# ESP32.net
KiCad netlist of a schematic drawn in Altium Designer
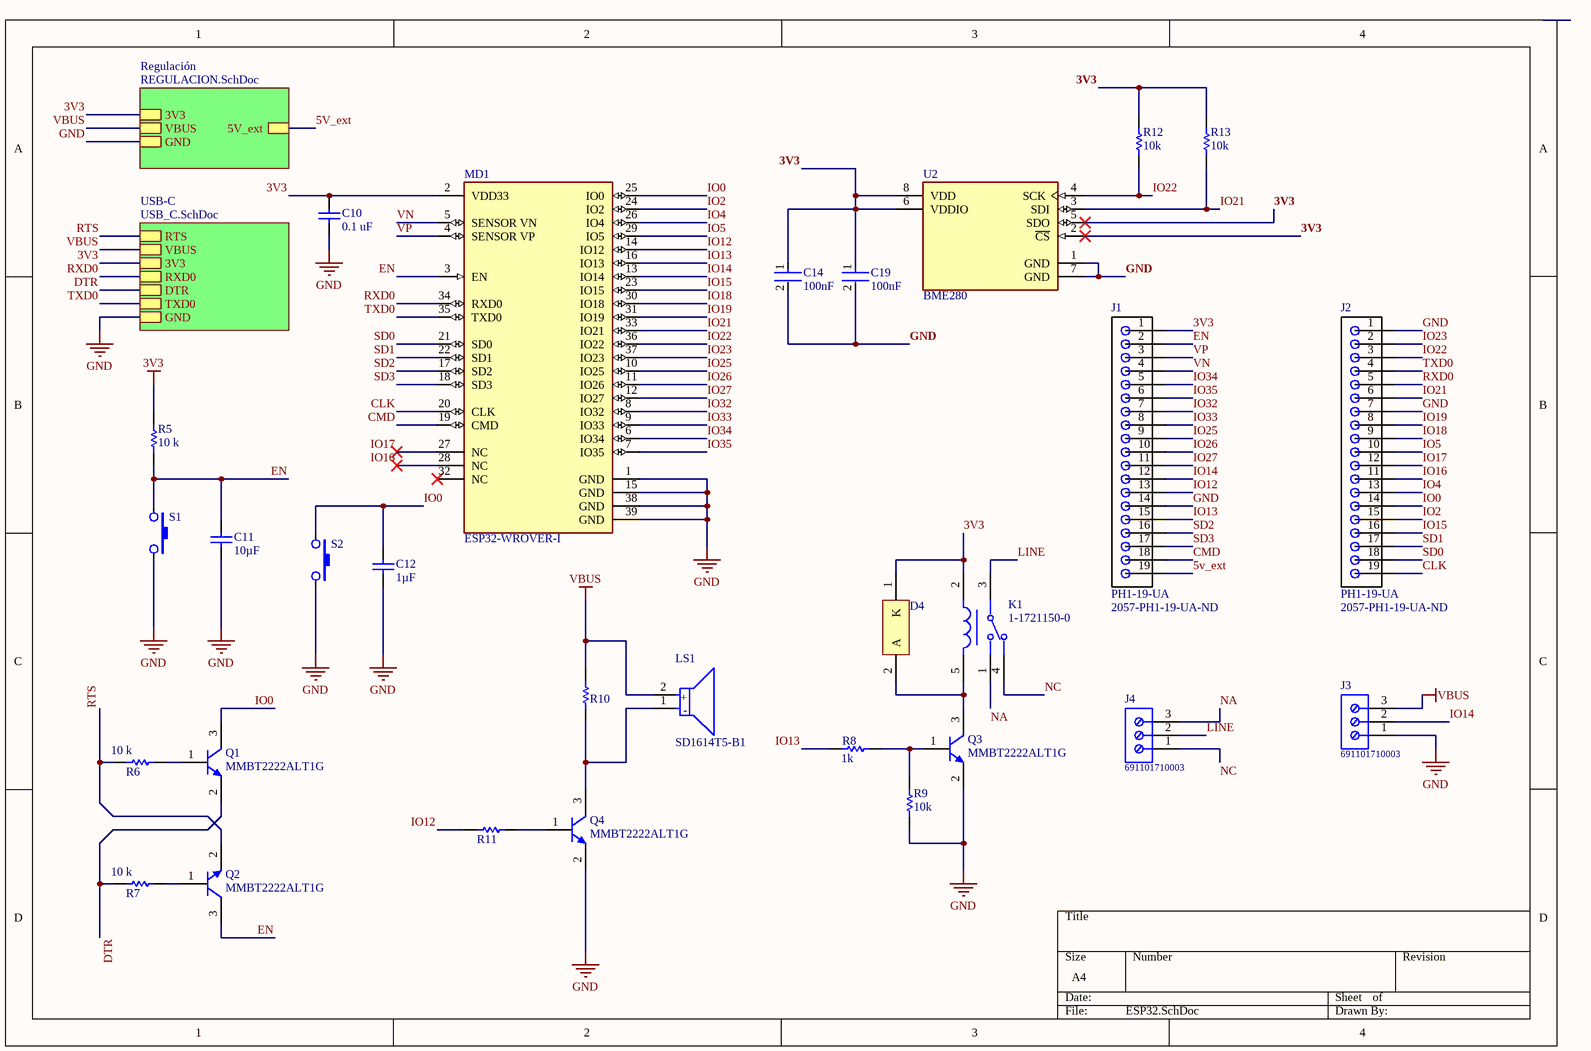
[diagram p0: ESP32.SchDoc]

(export (version "E")
  (design (tool "Eeschema 10.0.6"))
  (components
    (comp (ref "C10")
      (value "0.1 uF")
      (footprint "CAPC2013X94X50ML20T25")
      (description "Chip Capacitor, Ceramic, 0.1 uF, 10%, 50 V, 0805, RoHS, Tape and Reel")
      (fields (field (name "MANUFACTURER") "AVX"))
      (libsource (lib "Altium Content Vault") (part "CAP-NP-2"))
    )
    (comp (ref "C11")
      (value "10µF")
      (footprint "CAPC2013X145X50ML20T25")
      (description "1µF ±10% 16V Ceramic Capacitor X7R 0805 (2012 Metric)")
      (fields (field (name "MANUFACTURER") "Kemet") (field (name "PART NUMBER") "C0805C105K4RAC7800"))
      (libsource (lib "Altium Content Vault") (part "CAP"))
    )
    (comp (ref "C12")
      (value "1µF")
      (footprint "CAPC2013X145X50ML20T25")
      (description "1µF ±10% 16V Ceramic Capacitor X7R 0805 (2012 Metric)")
      (fields (field (name "MANUFACTURER") "Kemet") (field (name "PART NUMBER") "C0805C105K4RAC7800"))
      (libsource (lib "Altium Content Vault") (part "CAP"))
    )
    (comp (ref "C14")
      (value "100nF")
      (footprint "FP-C0805C-DN-IPC_A")
      (description "CAP CER 0.1UF 50V X7R 0805")
      (fields
        (field (name "MANUFACTURER PART NUMBER") "C0805C104K5RACTU")
        (field (name "MANUFACTURER") "KEMET")
      )
      (libsource (lib "Altium Content Vault") (part "b4654b650e69147ec39a6b967a45e02"))
    )
    (comp (ref "C19")
      (value "100nF")
      (footprint "FP-C0805C-DN-IPC_A")
      (description "CAP CER 0.1UF 50V X7R 0805")
      (fields
        (field (name "MANUFACTURER PART NUMBER") "C0805C104K5RACTU")
        (field (name "MANUFACTURER") "KEMET")
      )
      (libsource (lib "Altium Content Vault") (part "b4654b650e69147ec39a6b967a45e02"))
    )
    (comp (ref "D4")
      (value "MBR120ESFT1G")
      (footprint "ONSC-SOD-123FL-2-498_V")
      (description "Schottky Power Rectifier, 2-Pin SOD-123, Pb-Free, Tape and Reel")
      (fields (field (name "MANUFACTURER") "On Semiconductor"))
      (libsource (lib "Altium Content Vault") (part "ONSC-D-K1A2-2_A"))
    )
    (comp (ref "J1")
      (value "PH1-19-UA")
      (footprint "PH1-19-UA")
      (description "Connector Header Through Hole 19 position 0.100\" (2.54mm)")
      (fields (field (name "SUPPLIER PART NUMBER 1") "2057-PH1-19-UA-ND"))
      (libsource (lib "") (part "PH1-19-UA_1"))
    )
    (comp (ref "J2")
      (value "PH1-19-UA")
      (footprint "PH1-19-UA")
      (description "Connector Header Through Hole 19 position 0.100\" (2.54mm)")
      (fields (field (name "SUPPLIER PART NUMBER 1") "2057-PH1-19-UA-ND"))
      (libsource (lib "Isidro_Library") (part "PH1-19-UA"))
    )
    (comp (ref "J3")
      (value "691101710003")
      (footprint "691101710003")
      (description "Series 101 - 5.00 mm Horizontal Entry Modular with Pressure Clamp WR-TBL, 3 pin")
      (fields (field (name "MANUFACTURER") "Wurth Elektronik") (field (name "PUBLISHER") "WurthElektronik"))
      (libsource (lib "Altium Content Vault") (part "WE-CN-1P-F-TB3"))
    )
    (comp (ref "J4")
      (value "691101710003")
      (footprint "691101710003")
      (description "Series 101 - 5.00 mm Horizontal Entry Modular with Pressure Clamp WR-TBL, 3 pin")
      (fields (field (name "MANUFACTURER") "Wurth Elektronik") (field (name "PUBLISHER") "WurthElektronik"))
      (libsource (lib "Altium Content Vault") (part "WE-CN-1P-F-TB3"))
    )
    (comp (ref "K1")
      (value "1-1721150-0")
      (footprint "FP-1-1721150-0-MFG")
      (description "RELAY GEN PURPOSE SPDT 10A 5V")
      (fields
        (field (name "MANUFACTURER") "TE")
        (field (name "OCTOPART") "https://octopart.com/1-1721150-0-te+connectivity-41294869")
      )
      (libsource (lib "Altium Content Vault") (part "6d7f6cec76f9d90da65a396cf24d809"))
    )
    (comp (ref "LS1")
      (value "SD1614T5-B1")
      (footprint "FP-SD1614T5-B1-MFG")
      (description "AUDIO MAGNETIC XDCR 3-6V TH")
      (libsource (lib "Altium Content Vault") (part "f7ec632b6fea80cbef86dc3340f200c"))
    )
    (comp (ref "MD1")
      (value "ESP32-WROVER-I")
      (footprint "FP-ESP32-WROVER-I-MFG")
      (description "SMD MODULE, ESP32-D0WDQ6, 32MBIT")
      (fields
        (field (name "MANUFACTURER") "Espressif")
        (field (name "OCTOPART") "https://octopart.com/esp32-wrover-i-espressif+systems-89171349")
      )
      (libsource (lib "Altium Content Vault") (part "cbbb37af8bcfe61dfd46ac9418f0340"))
    )
    (comp (ref "Q1")
      (value "MMBT2222ALT1G")
      (footprint "ONSC-SOT-23-3-318-08_V")
      (description "General Purpose Transistor, NPN Silicon, 3-Pin SOT-23, Pb-Free, Tape and Reel")
      (fields (field (name "MANUFACTURER") "On Semiconductor"))
      (libsource (lib "Altium Content Vault") (part "ONSC-NPN-B1E2C3-3"))
    )
    (comp (ref "Q2")
      (value "MMBT2222ALT1G")
      (footprint "ONSC-SOT-23-3-318-08_V")
      (description "General Purpose Transistor, NPN Silicon, 3-Pin SOT-23, Pb-Free, Tape and Reel")
      (fields (field (name "MANUFACTURER") "On Semiconductor"))
      (libsource (lib "Altium Content Vault") (part "ONSC-NPN-B1E2C3-3"))
    )
    (comp (ref "Q3")
      (value "MMBT2222ALT1G")
      (footprint "ONSC-SOT-23-3-318-08_V")
      (description "General Purpose Transistor, NPN Silicon, 3-Pin SOT-23, Pb-Free, Tape and Reel")
      (fields (field (name "MANUFACTURER") "On Semiconductor"))
      (libsource (lib "Altium Content Vault") (part "ONSC-NPN-B1E2C3-3"))
    )
    (comp (ref "Q4")
      (value "MMBT2222ALT1G")
      (footprint "ONSC-SOT-23-3-318-08_V")
      (description "General Purpose Transistor, NPN Silicon, 3-Pin SOT-23, Pb-Free, Tape and Reel")
      (fields (field (name "MANUFACTURER") "On Semiconductor"))
      (libsource (lib "Altium Content Vault") (part "ONSC-NPN-B1E2C3-3"))
    )
    (comp (ref "R5")
      (value "10 k")
      (footprint "RESC2013X60X30ML20T20")
      (fields (field (name "PART NUMBER") "RK73B2ATTD103J") (field (name "MANUFACTURER") "KOA Speer"))
      (libsource (lib "Altium Content Vault") (part "RES"))
    )
    (comp (ref "R6")
      (value "10 k")
      (footprint "RESC2013X60X30ML20T20")
      (fields (field (name "PART NUMBER") "RK73B2ATTD103J") (field (name "MANUFACTURER") "KOA Speer"))
      (libsource (lib "Altium Content Vault") (part "RES"))
    )
    (comp (ref "R7")
      (value "10 k")
      (footprint "RESC2013X60X30ML20T20")
      (fields (field (name "PART NUMBER") "RK73B2ATTD103J") (field (name "MANUFACTURER") "KOA Speer"))
      (libsource (lib "Altium Content Vault") (part "RES"))
    )
    (comp (ref "R8")
      (value "1k")
      (footprint "RESC2013X60X30ML20T20")
      (fields (field (name "PART NUMBER") "RK73B2ATTD103J") (field (name "MANUFACTURER") "KOA Speer"))
      (libsource (lib "Altium Content Vault") (part "RES"))
    )
    (comp (ref "R9")
      (value "10k")
      (footprint "RESC2013X60X30ML20T20")
      (fields (field (name "PART NUMBER") "RK73B2ATTD103J") (field (name "MANUFACTURER") "KOA Speer"))
      (libsource (lib "Altium Content Vault") (part "RES"))
    )
    (comp (ref "R10")
      (value "ERJ-P06J102V")
      (footprint "RESC2013X70X40ML20T20")
      (description "RES SMD 1K OHM 5% 1/2W 0805")
      (fields (field (name "MANUFACTURER") "Panasonic"))
      (libsource (lib "Altium Content Vault") (part "RES"))
    )
    (comp (ref "R11")
      (value "RK73B2ATTD103J")
      (footprint "RESC2013X60X30ML20T20")
      (fields (field (name "MANUFACTURER") "KOA Speer"))
      (libsource (lib "Altium Content Vault") (part "RES"))
    )
    (comp (ref "R12")
      (value "10k")
      (footprint "RESC2013X60X40ML20T25_A")
      (fields (field (name "TOLERANCE") "0.1%") (field (name "MANUFACTURER") "Panasonic"))
      (libsource (lib "Altium Content Vault") (part "RES-2"))
    )
    (comp (ref "R13")
      (value "10k")
      (footprint "RESC2013X60X40ML20T25_A")
      (fields (field (name "TOLERANCE") "0.1%") (field (name "MANUFACTURER") "Panasonic"))
      (libsource (lib "Altium Content Vault") (part "RES-2"))
    )
    (comp (ref "S1")
      (value "PTS820J25MSMTRLFS")
      (footprint "SMT_SW_PTS_820")
      (libsource (lib "SnapEDAsch") (part "PTS820J25MSMTRLFS"))
    )
    (comp (ref "S2")
      (value "IO0")
      (footprint "SMT_SW_PTS_820")
      (libsource (lib "SnapEDAsch") (part "PTS820J25MSMTRLFS"))
    )
    (comp (ref "U2")
      (value "BME280")
      (footprint "FP-BME280-MFG")
      (description "SENSOR PRESSURE HUMIDITY TEMP")
      (libsource (lib "Altium Content Vault") (part "d58e2f6669bc67e6a2bc6a28610ca79"))
    )
  )
  (nets
    (net (code "2") (name "/5v_ext") (class "Default")
      (node (ref "J1") (pin "19") (pinfunction "19_19") (pintype "passive"))
    )
    (net (code "3") (name "/CLK") (class "Default")
      (node (ref "J2") (pin "19") (pinfunction "19_19") (pintype "passive"))
      (node (ref "MD1") (pin "20") (pinfunction "CLK_20") (pintype "bidirectional"))
    )
    (net (code "4") (name "/CMD") (class "Default")
      (node (ref "J1") (pin "18") (pinfunction "18_18") (pintype "passive"))
      (node (ref "MD1") (pin "19") (pinfunction "CMD_19") (pintype "bidirectional"))
    )
    (net (code "5") (name "/DTR") (class "Default")
      (node (ref "Q1") (pin "2") (pinfunction "E_2") (pintype "passive"))
      (node (ref "R7") (pin "2") (pinfunction "2_2") (pintype "passive"))
    )
    (net (code "6") (name "/EN") (class "Default")
      (node (ref "C11") (pin "2") (pinfunction "2_2") (pintype "passive"))
      (node (ref "J1") (pin "2") (pinfunction "2_2") (pintype "passive"))
      (node (ref "MD1") (pin "3") (pinfunction "EN_3") (pintype "input"))
      (node (ref "Q2") (pin "3") (pinfunction "C_3") (pintype "passive"))
      (node (ref "R5") (pin "1") (pinfunction "1_1") (pintype "passive"))
      (node (ref "S1") (pin "1") (pinfunction "1_1") (pintype "passive"))
    )
    (net (code "7") (name "/IO0") (class "Default")
      (node (ref "C12") (pin "2") (pinfunction "2_2") (pintype "passive"))
      (node (ref "J2") (pin "14") (pinfunction "14_14") (pintype "passive"))
      (node (ref "MD1") (pin "25") (pinfunction "IO0_25") (pintype "bidirectional"))
      (node (ref "Q1") (pin "3") (pinfunction "C_3") (pintype "passive"))
      (node (ref "S2") (pin "1") (pinfunction "1_1") (pintype "passive"))
    )
    (net (code "8") (name "/IO2") (class "Default")
      (node (ref "J2") (pin "15") (pinfunction "15_15") (pintype "passive"))
      (node (ref "MD1") (pin "24") (pinfunction "IO2_24") (pintype "bidirectional"))
    )
    (net (code "9") (name "/IO4") (class "Default")
      (node (ref "J2") (pin "13") (pinfunction "13_13") (pintype "passive"))
      (node (ref "MD1") (pin "26") (pinfunction "IO4_26") (pintype "bidirectional"))
    )
    (net (code "10") (name "/IO5") (class "Default")
      (node (ref "J2") (pin "10") (pinfunction "10_10") (pintype "passive"))
      (node (ref "MD1") (pin "29") (pinfunction "IO5_29") (pintype "bidirectional"))
    )
    (net (code "11") (name "/IO12") (class "Default")
      (node (ref "J1") (pin "13") (pinfunction "13_13") (pintype "passive"))
      (node (ref "MD1") (pin "14") (pinfunction "IO12_14") (pintype "bidirectional"))
      (node (ref "R11") (pin "1") (pinfunction "1_1") (pintype "passive"))
    )
    (net (code "12") (name "/IO13") (class "Default")
      (node (ref "J1") (pin "15") (pinfunction "15_15") (pintype "passive"))
      (node (ref "MD1") (pin "16") (pinfunction "IO13_16") (pintype "bidirectional"))
      (node (ref "R8") (pin "1") (pinfunction "1_1") (pintype "passive"))
    )
    (net (code "13") (name "/IO14") (class "Default")
      (node (ref "J1") (pin "12") (pinfunction "12_12") (pintype "passive"))
      (node (ref "J3") (pin "2") (pinfunction "2_2") (pintype "passive"))
      (node (ref "MD1") (pin "13") (pinfunction "IO14_13") (pintype "bidirectional"))
    )
    (net (code "14") (name "/IO15") (class "Default")
      (node (ref "J2") (pin "16") (pinfunction "16_16") (pintype "passive"))
      (node (ref "MD1") (pin "23") (pinfunction "IO15_23") (pintype "bidirectional"))
    )
    (net (code "15") (name "/IO16") (class "Default")
      (node (ref "J2") (pin "11") (pinfunction "11_11") (pintype "passive"))
      (node (ref "MD1") (pin "28") (pinfunction "NC_28") (pintype "passive"))
    )
    (net (code "16") (name "/IO17") (class "Default")
      (node (ref "J2") (pin "12") (pinfunction "12_12") (pintype "passive"))
      (node (ref "MD1") (pin "27") (pinfunction "NC_27") (pintype "passive"))
    )
    (net (code "17") (name "/IO18") (class "Default")
      (node (ref "J2") (pin "9") (pinfunction "9_9") (pintype "passive"))
      (node (ref "MD1") (pin "30") (pinfunction "IO18_30") (pintype "bidirectional"))
    )
    (net (code "18") (name "/IO19") (class "Default")
      (node (ref "J2") (pin "8") (pinfunction "8_8") (pintype "passive"))
      (node (ref "MD1") (pin "31") (pinfunction "IO19_31") (pintype "bidirectional"))
    )
    (net (code "19") (name "/IO21") (class "Default")
      (node (ref "J2") (pin "6") (pinfunction "6_6") (pintype "passive"))
      (node (ref "MD1") (pin "33") (pinfunction "IO21_33") (pintype "bidirectional"))
      (node (ref "R13") (pin "1") (pinfunction "1_1") (pintype "passive"))
      (node (ref "U2") (pin "3") (pinfunction "SDI_3") (pintype "bidirectional"))
    )
    (net (code "20") (name "/IO22") (class "Default")
      (node (ref "J2") (pin "3") (pinfunction "3_3") (pintype "passive"))
      (node (ref "MD1") (pin "36") (pinfunction "IO22_36") (pintype "bidirectional"))
      (node (ref "R12") (pin "1") (pinfunction "1_1") (pintype "passive"))
      (node (ref "U2") (pin "4") (pinfunction "SCK_4") (pintype "input"))
    )
    (net (code "21") (name "/IO23") (class "Default")
      (node (ref "J2") (pin "2") (pinfunction "2_2") (pintype "passive"))
      (node (ref "MD1") (pin "37") (pinfunction "IO23_37") (pintype "bidirectional"))
    )
    (net (code "22") (name "/IO25") (class "Default")
      (node (ref "J1") (pin "9") (pinfunction "9_9") (pintype "passive"))
      (node (ref "MD1") (pin "10") (pinfunction "IO25_10") (pintype "bidirectional"))
    )
    (net (code "23") (name "/IO26") (class "Default")
      (node (ref "J1") (pin "10") (pinfunction "10_10") (pintype "passive"))
      (node (ref "MD1") (pin "11") (pinfunction "IO26_11") (pintype "bidirectional"))
    )
    (net (code "24") (name "/IO27") (class "Default")
      (node (ref "J1") (pin "11") (pinfunction "11_11") (pintype "passive"))
      (node (ref "MD1") (pin "12") (pinfunction "IO27_12") (pintype "bidirectional"))
    )
    (net (code "25") (name "/IO32") (class "Default")
      (node (ref "J1") (pin "7") (pinfunction "7_7") (pintype "passive"))
      (node (ref "MD1") (pin "8") (pinfunction "IO32_8") (pintype "bidirectional"))
    )
    (net (code "26") (name "/IO33") (class "Default")
      (node (ref "J1") (pin "8") (pinfunction "8_8") (pintype "passive"))
      (node (ref "MD1") (pin "9") (pinfunction "IO33_9") (pintype "bidirectional"))
    )
    (net (code "27") (name "/IO34") (class "Default")
      (node (ref "J1") (pin "5") (pinfunction "5_5") (pintype "passive"))
      (node (ref "MD1") (pin "6") (pinfunction "IO34_6") (pintype "bidirectional"))
    )
    (net (code "28") (name "/IO35") (class "Default")
      (node (ref "J1") (pin "6") (pinfunction "6_6") (pintype "passive"))
      (node (ref "MD1") (pin "7") (pinfunction "IO35_7") (pintype "bidirectional"))
    )
    (net (code "29") (name "/LINE") (class "Default")
      (node (ref "J4") (pin "2") (pinfunction "2_2") (pintype "passive"))
      (node (ref "K1") (pin "3") (pinfunction "3_3") (pintype "passive"))
    )
    (net (code "30") (name "/NA") (class "Default")
      (node (ref "J4") (pin "3") (pinfunction "3_3") (pintype "passive"))
      (node (ref "K1") (pin "1") (pinfunction "1_1") (pintype "passive"))
    )
    (net (code "31") (name "/NC") (class "Default")
      (node (ref "J4") (pin "1") (pinfunction "1_1") (pintype "passive"))
      (node (ref "K1") (pin "4") (pinfunction "4_4") (pintype "passive"))
    )
    (net (code "32") (name "/RTS") (class "Default")
      (node (ref "Q2") (pin "2") (pinfunction "E_2") (pintype "passive"))
      (node (ref "R6") (pin "2") (pinfunction "2_2") (pintype "passive"))
    )
    (net (code "33") (name "/RXD0") (class "Default")
      (node (ref "J2") (pin "5") (pinfunction "5_5") (pintype "passive"))
      (node (ref "MD1") (pin "34") (pinfunction "RXD0_34") (pintype "bidirectional"))
    )
    (net (code "34") (name "/SD0") (class "Default")
      (node (ref "J2") (pin "18") (pinfunction "18_18") (pintype "passive"))
      (node (ref "MD1") (pin "21") (pinfunction "SD0_21") (pintype "bidirectional"))
    )
    (net (code "35") (name "/SD1") (class "Default")
      (node (ref "J2") (pin "17") (pinfunction "17_17") (pintype "passive"))
      (node (ref "MD1") (pin "22") (pinfunction "SD1_22") (pintype "bidirectional"))
    )
    (net (code "36") (name "/SD2") (class "Default")
      (node (ref "J1") (pin "16") (pinfunction "16_16") (pintype "passive"))
      (node (ref "MD1") (pin "17") (pinfunction "SD2_17") (pintype "bidirectional"))
    )
    (net (code "37") (name "/SD3") (class "Default")
      (node (ref "J1") (pin "17") (pinfunction "17_17") (pintype "passive"))
      (node (ref "MD1") (pin "18") (pinfunction "SD3_18") (pintype "bidirectional"))
    )
    (net (code "38") (name "/TXD0") (class "Default")
      (node (ref "J2") (pin "4") (pinfunction "4_4") (pintype "passive"))
      (node (ref "MD1") (pin "35") (pinfunction "TXD0_35") (pintype "bidirectional"))
    )
    (net (code "39") (name "/VN") (class "Default")
      (node (ref "J1") (pin "4") (pinfunction "4_4") (pintype "passive"))
      (node (ref "MD1") (pin "5") (pinfunction "SENSOR_VN_5") (pintype "bidirectional"))
    )
    (net (code "40") (name "/VP") (class "Default")
      (node (ref "J1") (pin "3") (pinfunction "3_3") (pintype "passive"))
      (node (ref "MD1") (pin "4") (pinfunction "SENSOR_VP_4") (pintype "bidirectional"))
    )
    (net (code "41") (name "3V3") (class "Default")
      (node (ref "C10") (pin "2") (pinfunction "2_2") (pintype "passive"))
      (node (ref "C14") (pin "1") (pinfunction "1_1") (pintype "passive"))
      (node (ref "C19") (pin "1") (pinfunction "1_1") (pintype "passive"))
      (node (ref "D4") (pin "1") (pinfunction "K_1") (pintype "passive"))
      (node (ref "J1") (pin "1") (pinfunction "1_1") (pintype "passive"))
      (node (ref "K1") (pin "2") (pinfunction "2_2") (pintype "passive"))
      (node (ref "MD1") (pin "2") (pinfunction "VDD33_2") (pintype "power_in"))
      (node (ref "R12") (pin "2") (pinfunction "2_2") (pintype "passive"))
      (node (ref "R13") (pin "2") (pinfunction "2_2") (pintype "passive"))
      (node (ref "R5") (pin "2") (pinfunction "2_2") (pintype "passive"))
      (node (ref "U2") (pin "2") (pinfunction "~{CS}_2") (pintype "input"))
      (node (ref "U2") (pin "5") (pinfunction "SDO_5") (pintype "bidirectional"))
      (node (ref "U2") (pin "6") (pinfunction "VDDIO_6") (pintype "power_in"))
      (node (ref "U2") (pin "8") (pinfunction "VDD_8") (pintype "power_in"))
    )
    (net (code "42") (name "GND") (class "Default")
      (node (ref "C10") (pin "1") (pinfunction "1_1") (pintype "passive"))
      (node (ref "C11") (pin "1") (pinfunction "1_1") (pintype "passive"))
      (node (ref "C12") (pin "1") (pinfunction "1_1") (pintype "passive"))
      (node (ref "C14") (pin "2") (pinfunction "2_2") (pintype "passive"))
      (node (ref "C19") (pin "2") (pinfunction "2_2") (pintype "passive"))
      (node (ref "J1") (pin "14") (pinfunction "14_14") (pintype "passive"))
      (node (ref "J2") (pin "1") (pinfunction "1_1") (pintype "passive"))
      (node (ref "J2") (pin "7") (pinfunction "7_7") (pintype "passive"))
      (node (ref "J3") (pin "1") (pinfunction "1_1") (pintype "passive"))
      (node (ref "MD1") (pin "1") (pinfunction "GND_1") (pintype "power_in"))
      (node (ref "MD1") (pin "15") (pinfunction "GND_15") (pintype "power_in"))
      (node (ref "MD1") (pin "38") (pinfunction "GND_38") (pintype "power_in"))
      (node (ref "MD1") (pin "39") (pinfunction "GND_39") (pintype "power_in"))
      (node (ref "Q3") (pin "2") (pinfunction "E_2") (pintype "passive"))
      (node (ref "Q4") (pin "2") (pinfunction "E_2") (pintype "passive"))
      (node (ref "R9") (pin "2") (pinfunction "2_2") (pintype "passive"))
      (node (ref "S1") (pin "2") (pinfunction "2_2") (pintype "passive"))
      (node (ref "S2") (pin "2") (pinfunction "2_2") (pintype "passive"))
      (node (ref "U2") (pin "1") (pinfunction "GND_1") (pintype "power_in"))
      (node (ref "U2") (pin "7") (pinfunction "GND_7") (pintype "power_in"))
    )
    (net (code "43") (name "Net-(D4-A)") (class "Default")
      (node (ref "D4") (pin "2") (pinfunction "A_2") (pintype "passive"))
      (node (ref "K1") (pin "5") (pinfunction "5_5") (pintype "passive"))
      (node (ref "Q3") (pin "3") (pinfunction "C_3") (pintype "passive"))
    )
    (net (code "44") (name "Net-(LS1-C)") (class "Default")
      (node (ref "LS1") (pin "1") (pinfunction "C_1") (pintype "passive"))
      (node (ref "Q4") (pin "3") (pinfunction "C_3") (pintype "passive"))
      (node (ref "R10") (pin "1") (pinfunction "1_1") (pintype "passive"))
    )
    (net (code "45") (name "Net-(Q1-B)") (class "Default")
      (node (ref "Q1") (pin "1") (pinfunction "B_1") (pintype "passive"))
      (node (ref "R6") (pin "1") (pinfunction "1_1") (pintype "passive"))
    )
    (net (code "46") (name "Net-(Q2-B)") (class "Default")
      (node (ref "Q2") (pin "1") (pinfunction "B_1") (pintype "passive"))
      (node (ref "R7") (pin "1") (pinfunction "1_1") (pintype "passive"))
    )
    (net (code "47") (name "Net-(Q3-B)") (class "Default")
      (node (ref "Q3") (pin "1") (pinfunction "B_1") (pintype "passive"))
      (node (ref "R8") (pin "2") (pinfunction "2_2") (pintype "passive"))
      (node (ref "R9") (pin "1") (pinfunction "1_1") (pintype "passive"))
    )
    (net (code "48") (name "Net-(Q4-B)") (class "Default")
      (node (ref "Q4") (pin "1") (pinfunction "B_1") (pintype "passive"))
      (node (ref "R11") (pin "2") (pinfunction "2_2") (pintype "passive"))
    )
    (net (code "49") (name "VBUS") (class "Default")
      (node (ref "J3") (pin "3") (pinfunction "3_3") (pintype "passive"))
      (node (ref "LS1") (pin "2") (pinfunction "A_2") (pintype "passive"))
      (node (ref "R10") (pin "2") (pinfunction "2_2") (pintype "passive"))
    )
    (net (code "50") (name "unconnected-(MD1-NC-Pad32)") (class "Default")
      (node (ref "MD1") (pin "32") (pinfunction "NC_32") (pintype "passive+no_connect"))
    )
  )
)
